# Expansion_Connector.net
KiCad netlist of a schematic drawn in Altium Designer
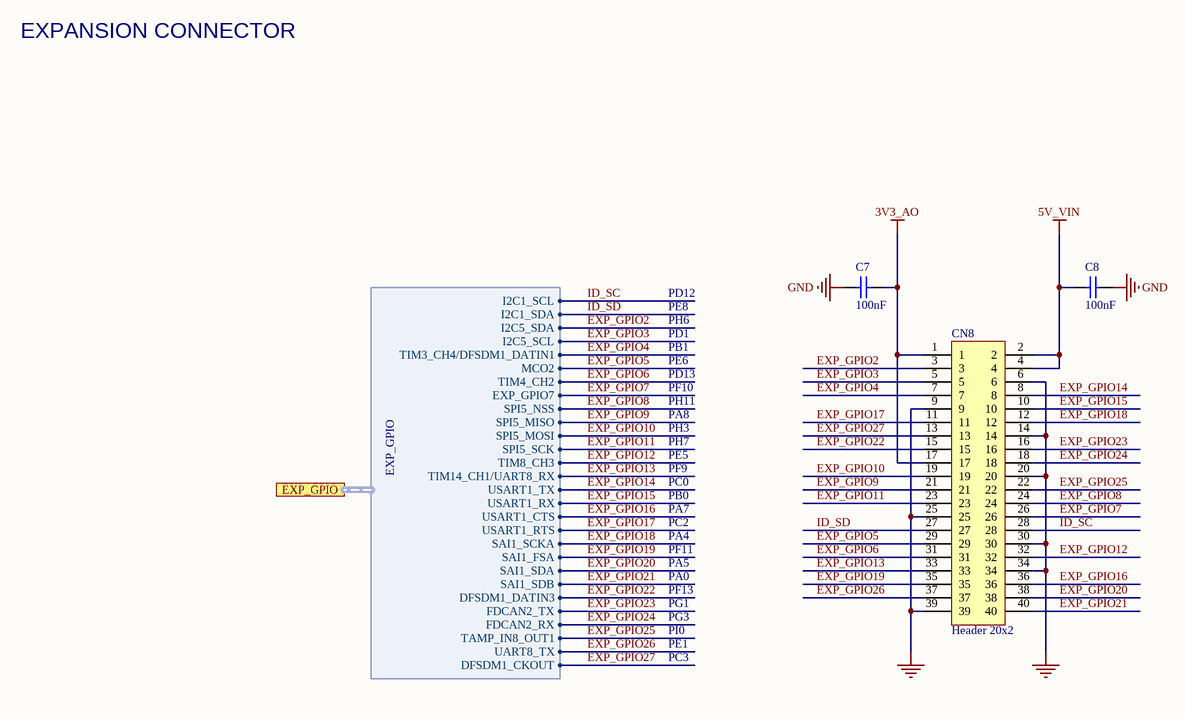
[diagram p0: Expansion_Connector.SchDoc]

(export (version "E")
  (design (tool "Eeschema 10.0.6"))
  (components
    (comp (ref "C7")
      (value "100nF")
      (footprint "C0402")
      (description "Capacitor, MLCC, 100nF, 16V, X7R, +/-10%, 0402, T=0.5mm")
      (fields (field (name "INTERNAL_PART_NUMBER") "MCD-00006") (field (name "MANUFACTURER") "YAGEO"))
      (libsource (lib "MCD_PARTS_database") (part "Capacitor"))
    )
    (comp (ref "C8")
      (value "100nF")
      (footprint "C0402")
      (description "Capacitor, MLCC, 100nF, 16V, X7R, +/-10%, 0402, T=0.5mm")
      (fields (field (name "INTERNAL_PART_NUMBER") "MCD-00006") (field (name "MANUFACTURER") "YAGEO"))
      (libsource (lib "MCD_PARTS_database") (part "Capacitor"))
    )
    (comp (ref "CN8")
      (value "Header 20x2")
      (footprint "CON_SAMTEC_TSW-120-07-G-D")
      (description "Header, 20x2, 2.54mm, VR, TH, T=5.84mm/2.54mm")
      (fields
        (field (name "INTERNAL_PART_NUMBER") "MCD-00302")
        (field (name "MANUFACTURER_PART_NUMBER") "TSW-120-07-G-D")
      )
      (libsource (lib "MCD_PARTS_database") (part "Header 20x2"))
    )
  )
  (nets
    (net (code "2") (name "/EXP_GPIO2") (class "Default")
      (node (ref "CN8") (pin "3") (pinfunction "3_3") (pintype "passive"))
    )
    (net (code "3") (name "/EXP_GPIO3") (class "Default")
      (node (ref "CN8") (pin "5") (pinfunction "5_5") (pintype "passive"))
    )
    (net (code "4") (name "/EXP_GPIO4") (class "Default")
      (node (ref "CN8") (pin "7") (pinfunction "7_7") (pintype "passive"))
    )
    (net (code "5") (name "/EXP_GPIO5") (class "Default")
      (node (ref "CN8") (pin "29") (pinfunction "29_29") (pintype "passive"))
    )
    (net (code "6") (name "/EXP_GPIO6") (class "Default")
      (node (ref "CN8") (pin "31") (pinfunction "31_31") (pintype "passive"))
    )
    (net (code "7") (name "/EXP_GPIO7") (class "Default")
      (node (ref "CN8") (pin "26") (pinfunction "26_26") (pintype "passive"))
    )
    (net (code "8") (name "/EXP_GPIO8") (class "Default")
      (node (ref "CN8") (pin "24") (pinfunction "24_24") (pintype "passive"))
    )
    (net (code "9") (name "/EXP_GPIO9") (class "Default")
      (node (ref "CN8") (pin "21") (pinfunction "21_21") (pintype "passive"))
    )
    (net (code "10") (name "/EXP_GPIO10") (class "Default")
      (node (ref "CN8") (pin "19") (pinfunction "19_19") (pintype "passive"))
    )
    (net (code "11") (name "/EXP_GPIO11") (class "Default")
      (node (ref "CN8") (pin "23") (pinfunction "23_23") (pintype "passive"))
    )
    (net (code "12") (name "/EXP_GPIO12") (class "Default")
      (node (ref "CN8") (pin "32") (pinfunction "32_32") (pintype "passive"))
    )
    (net (code "13") (name "/EXP_GPIO13") (class "Default")
      (node (ref "CN8") (pin "33") (pinfunction "33_33") (pintype "passive"))
    )
    (net (code "14") (name "/EXP_GPIO14") (class "Default")
      (node (ref "CN8") (pin "8") (pinfunction "8_8") (pintype "passive"))
    )
    (net (code "15") (name "/EXP_GPIO15") (class "Default")
      (node (ref "CN8") (pin "10") (pinfunction "10_10") (pintype "passive"))
    )
    (net (code "16") (name "/EXP_GPIO16") (class "Default")
      (node (ref "CN8") (pin "36") (pinfunction "36_36") (pintype "passive"))
    )
    (net (code "17") (name "/EXP_GPIO17") (class "Default")
      (node (ref "CN8") (pin "11") (pinfunction "11_11") (pintype "passive"))
    )
    (net (code "18") (name "/EXP_GPIO18") (class "Default")
      (node (ref "CN8") (pin "12") (pinfunction "12_12") (pintype "passive"))
    )
    (net (code "19") (name "/EXP_GPIO19") (class "Default")
      (node (ref "CN8") (pin "35") (pinfunction "35_35") (pintype "passive"))
    )
    (net (code "20") (name "/EXP_GPIO20") (class "Default")
      (node (ref "CN8") (pin "38") (pinfunction "38_38") (pintype "passive"))
    )
    (net (code "21") (name "/EXP_GPIO21") (class "Default")
      (node (ref "CN8") (pin "40") (pinfunction "40_40") (pintype "passive"))
    )
    (net (code "22") (name "/EXP_GPIO22") (class "Default")
      (node (ref "CN8") (pin "15") (pinfunction "15_15") (pintype "passive"))
    )
    (net (code "23") (name "/EXP_GPIO23") (class "Default")
      (node (ref "CN8") (pin "16") (pinfunction "16_16") (pintype "passive"))
    )
    (net (code "24") (name "/EXP_GPIO24") (class "Default")
      (node (ref "CN8") (pin "18") (pinfunction "18_18") (pintype "passive"))
    )
    (net (code "25") (name "/EXP_GPIO25") (class "Default")
      (node (ref "CN8") (pin "22") (pinfunction "22_22") (pintype "passive"))
    )
    (net (code "26") (name "/EXP_GPIO26") (class "Default")
      (node (ref "CN8") (pin "37") (pinfunction "37_37") (pintype "passive"))
    )
    (net (code "27") (name "/EXP_GPIO27") (class "Default")
      (node (ref "CN8") (pin "13") (pinfunction "13_13") (pintype "passive"))
    )
    (net (code "28") (name "/ID_SC") (class "Default")
      (node (ref "CN8") (pin "28") (pinfunction "28_28") (pintype "passive"))
    )
    (net (code "29") (name "/ID_SD") (class "Default")
      (node (ref "CN8") (pin "27") (pinfunction "27_27") (pintype "passive"))
    )
    (net (code "31") (name "3V3_AO") (class "Default")
      (node (ref "C7") (pin "1") (pinfunction "1_1") (pintype "passive"))
      (node (ref "CN8") (pin "1") (pinfunction "1_1") (pintype "passive"))
      (node (ref "CN8") (pin "17") (pinfunction "17_17") (pintype "passive"))
    )
    (net (code "32") (name "5V_VIN") (class "Default")
      (node (ref "C8") (pin "2") (pinfunction "2_2") (pintype "passive"))
      (node (ref "CN8") (pin "2") (pinfunction "2_2") (pintype "passive"))
      (node (ref "CN8") (pin "4") (pinfunction "4_4") (pintype "passive"))
    )
    (net (code "33") (name "GND") (class "Default")
      (node (ref "C7") (pin "2") (pinfunction "2_2") (pintype "passive"))
      (node (ref "C8") (pin "1") (pinfunction "1_1") (pintype "passive"))
      (node (ref "CN8") (pin "14") (pinfunction "14_14") (pintype "passive"))
      (node (ref "CN8") (pin "20") (pinfunction "20_20") (pintype "passive"))
      (node (ref "CN8") (pin "25") (pinfunction "25_25") (pintype "passive"))
      (node (ref "CN8") (pin "30") (pinfunction "30_30") (pintype "passive"))
      (node (ref "CN8") (pin "34") (pinfunction "34_34") (pintype "passive"))
      (node (ref "CN8") (pin "39") (pinfunction "39_39") (pintype "passive"))
      (node (ref "CN8") (pin "6") (pinfunction "6_6") (pintype "passive"))
      (node (ref "CN8") (pin "9") (pinfunction "9_9") (pintype "passive"))
    )
  )
)
